# 485.net
KiCad netlist of a schematic drawn in Altium Designer
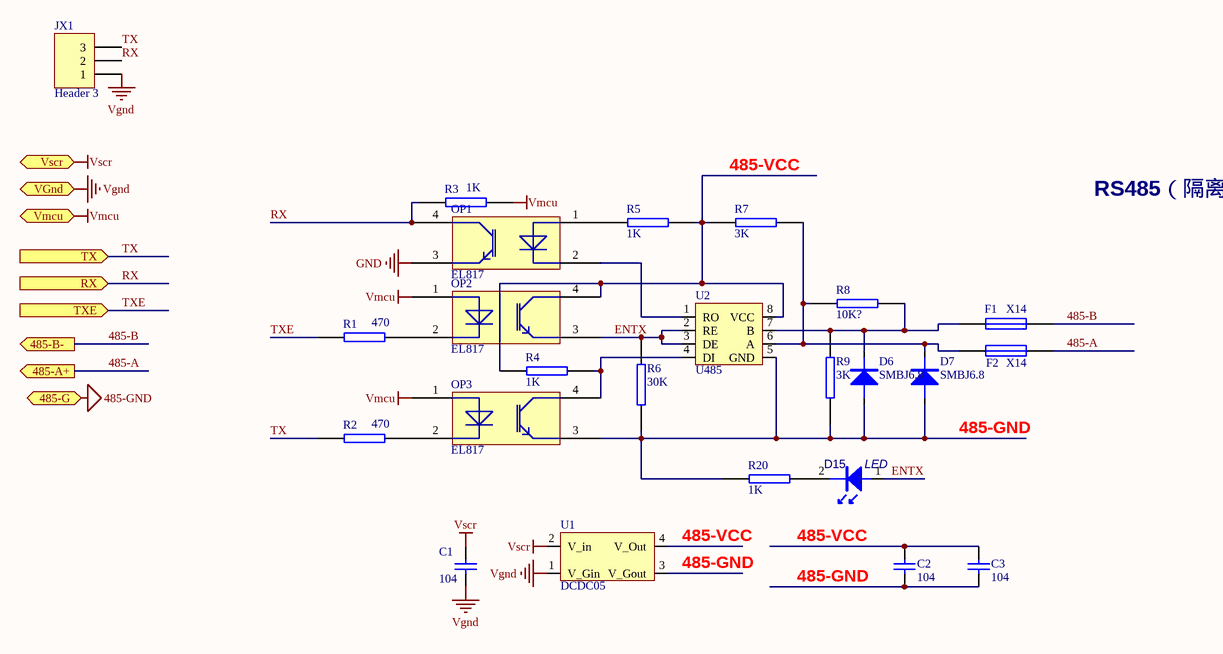
[diagram p0: 485.SchDoc]

(export (version "E")
  (design (tool "Eeschema 10.0.6"))
  (components
    (comp (ref "C1")
      (value "104")
      (footprint "C0805")
      (description "Capacitor")
      (fields (field (name "PUBLISHER") "Altium Limited"))
      (libsource (lib "Miscellaneous Devices") (part "Cap"))
    )
    (comp (ref "C2")
      (value "104")
      (footprint "C0805")
      (description "Capacitor")
      (fields (field (name "PUBLISHER") "Altium Limited"))
      (libsource (lib "Miscellaneous Devices") (part "Cap"))
    )
    (comp (ref "C3")
      (value "104")
      (footprint "C0805")
      (description "Capacitor")
      (fields (field (name "PUBLISHER") "Altium Limited"))
      (libsource (lib "Miscellaneous Devices") (part "Cap"))
    )
    (comp (ref "D6")
      (value "SMBJ6.8")
      (footprint "SMBJ_SMT")
      (description "Diode")
      (libsource (lib "*") (part "DIODE"))
    )
    (comp (ref "D7")
      (value "SMBJ6.8")
      (footprint "SMBJ_SMT")
      (description "Diode")
      (libsource (lib "*") (part "DIODE"))
    )
    (comp (ref "D15") (value "LED") (footprint "LED0805") (libsource (lib "*") (part "LED")))
    (comp (ref "F1")
      (value "X14")
      (footprint "PPTC_SMT")
      (description "Fuse")
      (fields (field (name "PUBLISHER") "Altium Limited"))
      (libsource (lib "Miscellaneous Devices") (part "Fuse 1"))
    )
    (comp (ref "F2")
      (value "X14")
      (footprint "PPTC_SMT")
      (description "Fuse")
      (fields (field (name "PUBLISHER") "Altium Limited"))
      (libsource (lib "Miscellaneous Devices") (part "Fuse 1"))
    )
    (comp (ref "JX1")
      (value "Header 3")
      (footprint "HDR1X3")
      (description "Header, 3-Pin")
      (fields (field (name "PUBLISHER") "Altium Limited"))
      (libsource (lib "Miscellaneous Connectors") (part "Header 3"))
    )
    (comp (ref "OP1")
      (value "EL817")
      (footprint "PS2701")
      (libsource (lib "altium-import") (part "root_0_mirrored__NDSCHLIB.SCHLIB"))
    )
    (comp (ref "OP2")
      (value "EL817")
      (footprint "PS2701")
      (libsource (lib "altium-import") (part "root_0__NDSCHLIB.SCHLIB"))
    )
    (comp (ref "OP3")
      (value "EL817")
      (footprint "PS2701")
      (libsource (lib "altium-import") (part "root_0__NDSCHLIB.SCHLIB"))
    )
    (comp (ref "R1") (value "470") (footprint "0805R") (libsource (lib "*") (part "RES2")))
    (comp (ref "R2") (value "470") (footprint "0805R") (libsource (lib "*") (part "RES2")))
    (comp (ref "R3") (value "1K") (footprint "0805R") (libsource (lib "*") (part "RES2")))
    (comp (ref "R4") (value "1K") (footprint "0805R") (libsource (lib "*") (part "RES2")))
    (comp (ref "R5") (value "1K") (footprint "0805R") (libsource (lib "*") (part "RES2")))
    (comp (ref "R6") (value "30K") (footprint "0805R") (libsource (lib "") (part "RES2_1")))
    (comp (ref "R7") (value "3K") (footprint "0805R") (libsource (lib "") (part "RES2_1")))
    (comp (ref "R8") (value "10K?") (footprint "0805R") (libsource (lib "") (part "RES2_1")))
    (comp (ref "R9") (value "3K") (footprint "0805R") (libsource (lib "") (part "RES2_1")))
    (comp (ref "R20") (value "1K") (footprint "0805R") (libsource (lib "*") (part "RES2")))
    (comp (ref "U1") (value "DCDC05") (footprint "VScore") (libsource (lib "POL485") (part "VScoure")))
    (comp (ref "U2") (value "U485") (footprint "SOP8") (libsource (lib "POL485") (part "U485")))
  )
  (nets
    (net (code "1") (name "/485-A") (class "Default")
      (node (ref "F2") (pin "1") (pinfunction "1_1") (pintype "passive"))
    )
    (net (code "2") (name "/485-B") (class "Default")
      (node (ref "F1") (pin "1") (pinfunction "1_1") (pintype "passive"))
    )
    (net (code "3") (name "/485-VCC") (class "Default")
      (node (ref "C2") (pin "2") (pinfunction "2_2") (pintype "passive"))
      (node (ref "C3") (pin "2") (pinfunction "2_2") (pintype "passive"))
      (node (ref "OP2") (pin "4") (pinfunction "4_4") (pintype "passive"))
      (node (ref "R4") (pin "1") (pinfunction "1_1") (pintype "passive"))
      (node (ref "R5") (pin "2") (pinfunction "2_2") (pintype "passive"))
      (node (ref "R7") (pin "2") (pinfunction "2_2") (pintype "passive"))
      (node (ref "U1") (pin "4") (pinfunction "V_Out_4") (pintype "passive"))
      (node (ref "U2") (pin "8") (pinfunction "VCC_8") (pintype "passive"))
    )
    (net (code "4") (name "/ENTX") (class "Default")
      (node (ref "D15") (pin "1") (pinfunction "1_1") (pintype "passive"))
      (node (ref "OP2") (pin "3") (pinfunction "3_3") (pintype "passive"))
      (node (ref "R6") (pin "2") (pinfunction "2_2") (pintype "passive"))
      (node (ref "U2") (pin "2") (pinfunction "RE_2") (pintype "passive"))
      (node (ref "U2") (pin "3") (pinfunction "DE_3") (pintype "passive"))
    )
    (net (code "5") (name "/RX") (class "Default")
      (node (ref "JX1") (pin "2") (pinfunction "2_2") (pintype "passive"))
      (node (ref "OP1") (pin "4") (pinfunction "4_4") (pintype "passive"))
      (node (ref "R3") (pin "2") (pinfunction "2_2") (pintype "passive"))
    )
    (net (code "6") (name "/TX") (class "Default")
      (node (ref "JX1") (pin "3") (pinfunction "3_3") (pintype "passive"))
      (node (ref "R2") (pin "2") (pinfunction "2_2") (pintype "passive"))
    )
    (net (code "7") (name "/TXE") (class "Default")
      (node (ref "R1") (pin "2") (pinfunction "2_2") (pintype "passive"))
    )
    (net (code "8") (name "485-GND") (class "Default")
      (node (ref "C2") (pin "1") (pinfunction "1_1") (pintype "passive"))
      (node (ref "C3") (pin "1") (pinfunction "1_1") (pintype "passive"))
      (node (ref "D6") (pin "A") (pinfunction "A_A") (pintype "passive"))
      (node (ref "D7") (pin "A") (pinfunction "A_A") (pintype "passive"))
      (node (ref "OP3") (pin "3") (pinfunction "3_3") (pintype "passive"))
      (node (ref "R20") (pin "1") (pinfunction "1_1") (pintype "passive"))
      (node (ref "R6") (pin "1") (pinfunction "1_1") (pintype "passive"))
      (node (ref "R9") (pin "1") (pinfunction "1_1") (pintype "passive"))
      (node (ref "U1") (pin "3") (pinfunction "V_Gout_3") (pintype "passive"))
      (node (ref "U2") (pin "5") (pinfunction "GND_5") (pintype "passive"))
    )
    (net (code "9") (name "GND") (class "Default")
      (node (ref "OP1") (pin "3") (pinfunction "3_3") (pintype "passive"))
    )
    (net (code "10") (name "Net-(D15-Pad2)") (class "Default")
      (node (ref "D15") (pin "2") (pinfunction "2_2") (pintype "passive"))
      (node (ref "R20") (pin "2") (pinfunction "2_2") (pintype "passive"))
    )
    (net (code "11") (name "Net-(OP1-Pad1)") (class "Default")
      (node (ref "OP1") (pin "1") (pinfunction "1_1") (pintype "passive"))
      (node (ref "R5") (pin "1") (pinfunction "1_1") (pintype "passive"))
    )
    (net (code "12") (name "Net-(OP2-Pad2)") (class "Default")
      (node (ref "OP2") (pin "2") (pinfunction "2_2") (pintype "passive"))
      (node (ref "R1") (pin "1") (pinfunction "1_1") (pintype "passive"))
    )
    (net (code "13") (name "Net-(OP3-Pad2)") (class "Default")
      (node (ref "OP3") (pin "2") (pinfunction "2_2") (pintype "passive"))
      (node (ref "R2") (pin "1") (pinfunction "1_1") (pintype "passive"))
    )
    (net (code "14") (name "Net-(U2-A)") (class "Default")
      (node (ref "D7") (pin "K") (pinfunction "K_K") (pintype "passive"))
      (node (ref "F2") (pin "2") (pinfunction "2_2") (pintype "passive"))
      (node (ref "R7") (pin "1") (pinfunction "1_1") (pintype "passive"))
      (node (ref "R8") (pin "2") (pinfunction "2_2") (pintype "passive"))
      (node (ref "U2") (pin "6") (pinfunction "A_6") (pintype "passive"))
    )
    (net (code "15") (name "Net-(U2-B)") (class "Default")
      (node (ref "D6") (pin "K") (pinfunction "K_K") (pintype "passive"))
      (node (ref "F1") (pin "2") (pinfunction "2_2") (pintype "passive"))
      (node (ref "R8") (pin "1") (pinfunction "1_1") (pintype "passive"))
      (node (ref "R9") (pin "2") (pinfunction "2_2") (pintype "passive"))
      (node (ref "U2") (pin "7") (pinfunction "B_7") (pintype "passive"))
    )
    (net (code "16") (name "Net-(U2-DI)") (class "Default")
      (node (ref "OP3") (pin "4") (pinfunction "4_4") (pintype "passive"))
      (node (ref "R4") (pin "2") (pinfunction "2_2") (pintype "passive"))
      (node (ref "U2") (pin "4") (pinfunction "DI_4") (pintype "passive"))
    )
    (net (code "17") (name "Net-(U2-RO)") (class "Default")
      (node (ref "OP1") (pin "2") (pinfunction "2_2") (pintype "passive"))
      (node (ref "U2") (pin "1") (pinfunction "RO_1") (pintype "passive"))
    )
    (net (code "18") (name "Vgnd") (class "Default")
      (node (ref "C1") (pin "1") (pinfunction "1_1") (pintype "passive"))
      (node (ref "JX1") (pin "1") (pinfunction "1_1") (pintype "passive"))
      (node (ref "U1") (pin "1") (pinfunction "V_Gin_1") (pintype "passive"))
    )
    (net (code "19") (name "Vmcu") (class "Default")
      (node (ref "OP2") (pin "1") (pinfunction "1_1") (pintype "passive"))
      (node (ref "OP3") (pin "1") (pinfunction "1_1") (pintype "passive"))
      (node (ref "R3") (pin "1") (pinfunction "1_1") (pintype "passive"))
    )
    (net (code "20") (name "Vscr") (class "Default")
      (node (ref "C1") (pin "2") (pinfunction "2_2") (pintype "passive"))
      (node (ref "U1") (pin "2") (pinfunction "V_in_2") (pintype "passive"))
    )
  )
)
